# board.net
KiCad netlist of a schematic drawn in EAGLE
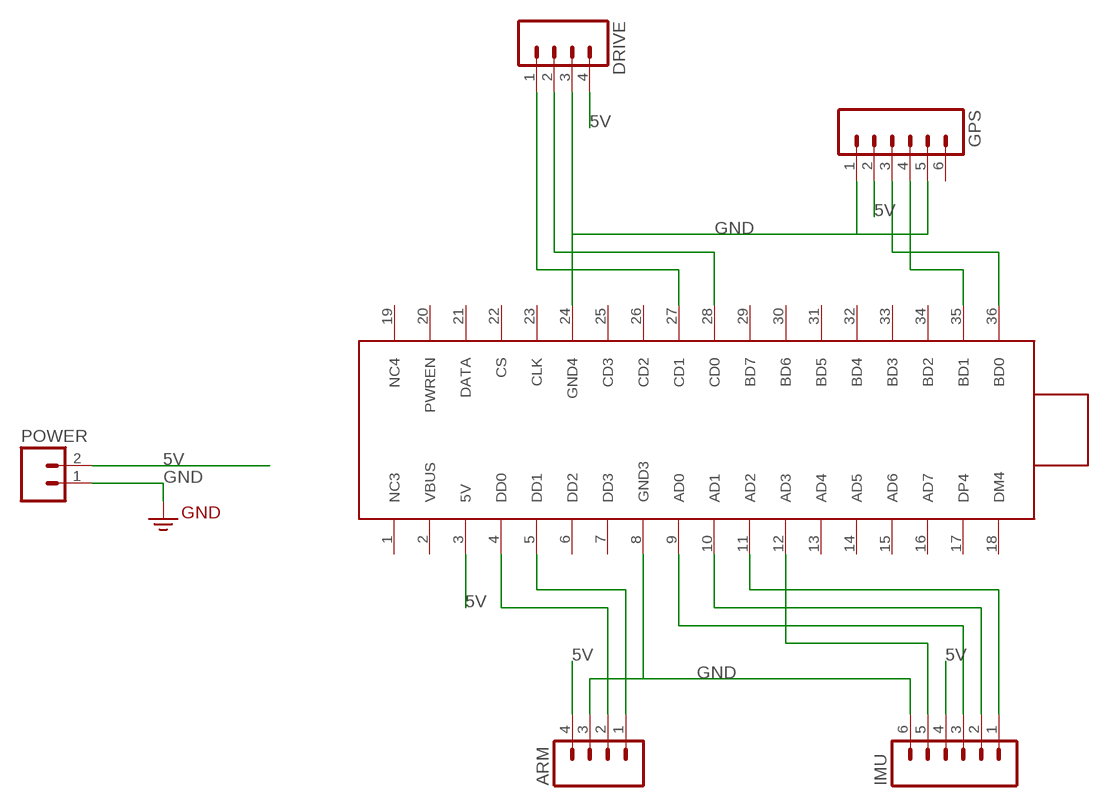
[diagram p0: schematic, sheet 1]

(export (version "E")
  (design (tool "Eeschema 10.0.6"))
  (components
    (comp (ref "ARM")
      (value "M04PTH")
      (footprint "eagle-import:1X04")
      (libsource (lib "eagle-import") (part "M04PTH"))
    )
    (comp (ref "DRIVE")
      (value "M04PTH")
      (footprint "eagle-import:1X04")
      (libsource (lib "eagle-import") (part "M04PTH"))
    )
    (comp (ref "GPS")
      (value "M06SILK_FEMALE_PTH")
      (footprint "eagle-import:1X06")
      (libsource (lib "eagle-import") (part "M06SILK_FEMALE_PTH"))
    )
    (comp (ref "IMU")
      (value "M06SILK_FEMALE_PTH")
      (footprint "eagle-import:1X06")
      (libsource (lib "eagle-import") (part "M06SILK_FEMALE_PTH"))
    )
    (comp (ref "POWER")
      (value "M02PTH")
      (footprint "eagle-import:1X02")
      (libsource (lib "eagle-import") (part "M02PTH"))
    )
    (comp (ref "U$1")
      (value "HUB")
      (footprint "eagle-import:HUB")
      (libsource (lib "eagle-import") (part "HUB"))
    )
  )
  (nets
    (net (code "1") (name "/5V") (class "Default")
      (node (ref "ARM") (pin "4") (pinfunction "4_4") (pintype "passive"))
      (node (ref "DRIVE") (pin "4") (pinfunction "4_4") (pintype "passive"))
      (node (ref "GPS") (pin "2") (pinfunction "2_2") (pintype "passive"))
      (node (ref "IMU") (pin "4") (pinfunction "4_4") (pintype "passive"))
      (node (ref "POWER") (pin "2") (pinfunction "2_2") (pintype "passive"))
      (node (ref "U$1") (pin "3") (pinfunction "5V_3") (pintype "bidirectional"))
    )
    (net (code "2") (name "GND2") (class "Default")
      (node (ref "ARM") (pin "3") (pinfunction "3_3") (pintype "passive"))
      (node (ref "DRIVE") (pin "3") (pinfunction "3_3") (pintype "passive"))
      (node (ref "GPS") (pin "1") (pinfunction "1_1") (pintype "passive"))
      (node (ref "GPS") (pin "5") (pinfunction "5_5") (pintype "passive"))
      (node (ref "IMU") (pin "6") (pinfunction "6_6") (pintype "passive"))
      (node (ref "POWER") (pin "1") (pinfunction "1_1") (pintype "passive"))
      (node (ref "U$1") (pin "24") (pinfunction "GND4_24") (pintype "bidirectional"))
      (node (ref "U$1") (pin "8") (pinfunction "GND3_8") (pintype "bidirectional"))
    )
    (net (code "3") (name "Net-(U$1-AD0)") (class "Default")
      (node (ref "IMU") (pin "3") (pinfunction "3_3") (pintype "passive"))
      (node (ref "U$1") (pin "9") (pinfunction "AD0_9") (pintype "bidirectional"))
    )
    (net (code "4") (name "Net-(U$1-AD1)") (class "Default")
      (node (ref "IMU") (pin "2") (pinfunction "2_2") (pintype "passive"))
      (node (ref "U$1") (pin "10") (pinfunction "AD1_10") (pintype "bidirectional"))
    )
    (net (code "5") (name "Net-(U$1-AD2)") (class "Default")
      (node (ref "IMU") (pin "1") (pinfunction "1_1") (pintype "passive"))
      (node (ref "U$1") (pin "11") (pinfunction "AD2_11") (pintype "bidirectional"))
    )
    (net (code "6") (name "Net-(U$1-AD3)") (class "Default")
      (node (ref "IMU") (pin "5") (pinfunction "5_5") (pintype "passive"))
      (node (ref "U$1") (pin "12") (pinfunction "AD3_12") (pintype "bidirectional"))
    )
    (net (code "7") (name "Net-(U$1-BD0)") (class "Default")
      (node (ref "GPS") (pin "3") (pinfunction "3_3") (pintype "passive"))
      (node (ref "U$1") (pin "36") (pinfunction "BD0_36") (pintype "bidirectional"))
    )
    (net (code "8") (name "Net-(U$1-BD1)") (class "Default")
      (node (ref "GPS") (pin "4") (pinfunction "4_4") (pintype "passive"))
      (node (ref "U$1") (pin "35") (pinfunction "BD1_35") (pintype "bidirectional"))
    )
    (net (code "9") (name "Net-(U$1-CD0)") (class "Default")
      (node (ref "DRIVE") (pin "2") (pinfunction "2_2") (pintype "passive"))
      (node (ref "U$1") (pin "28") (pinfunction "CD0_28") (pintype "bidirectional"))
    )
    (net (code "10") (name "Net-(U$1-CD1)") (class "Default")
      (node (ref "DRIVE") (pin "1") (pinfunction "1_1") (pintype "passive"))
      (node (ref "U$1") (pin "27") (pinfunction "CD1_27") (pintype "bidirectional"))
    )
    (net (code "11") (name "Net-(U$1-DD0)") (class "Default")
      (node (ref "ARM") (pin "2") (pinfunction "2_2") (pintype "passive"))
      (node (ref "U$1") (pin "4") (pinfunction "DD0_4") (pintype "bidirectional"))
    )
    (net (code "12") (name "Net-(U$1-DD1)") (class "Default")
      (node (ref "ARM") (pin "1") (pinfunction "1_1") (pintype "passive"))
      (node (ref "U$1") (pin "5") (pinfunction "DD1_5") (pintype "bidirectional"))
    )
    (net (code "13") (name "unconnected-(GPS-Pad6)") (class "Default")
      (node (ref "GPS") (pin "6") (pinfunction "6_6") (pintype "passive"))
    )
    (net (code "14") (name "unconnected-(U$1-AD4-Pad13)") (class "Default")
      (node (ref "U$1") (pin "13") (pinfunction "AD4_13") (pintype "bidirectional"))
    )
    (net (code "15") (name "unconnected-(U$1-AD5-Pad14)") (class "Default")
      (node (ref "U$1") (pin "14") (pinfunction "AD5_14") (pintype "bidirectional"))
    )
    (net (code "16") (name "unconnected-(U$1-AD6-Pad15)") (class "Default")
      (node (ref "U$1") (pin "15") (pinfunction "AD6_15") (pintype "bidirectional"))
    )
    (net (code "17") (name "unconnected-(U$1-AD7-Pad16)") (class "Default")
      (node (ref "U$1") (pin "16") (pinfunction "AD7_16") (pintype "bidirectional"))
    )
    (net (code "18") (name "unconnected-(U$1-BD2-Pad34)") (class "Default")
      (node (ref "U$1") (pin "34") (pinfunction "BD2_34") (pintype "bidirectional"))
    )
    (net (code "19") (name "unconnected-(U$1-BD3-Pad33)") (class "Default")
      (node (ref "U$1") (pin "33") (pinfunction "BD3_33") (pintype "bidirectional"))
    )
    (net (code "20") (name "unconnected-(U$1-BD4-Pad32)") (class "Default")
      (node (ref "U$1") (pin "32") (pinfunction "BD4_32") (pintype "bidirectional"))
    )
    (net (code "21") (name "unconnected-(U$1-BD5-Pad31)") (class "Default")
      (node (ref "U$1") (pin "31") (pinfunction "BD5_31") (pintype "bidirectional"))
    )
    (net (code "22") (name "unconnected-(U$1-BD6-Pad30)") (class "Default")
      (node (ref "U$1") (pin "30") (pinfunction "BD6_30") (pintype "bidirectional"))
    )
    (net (code "23") (name "unconnected-(U$1-BD7-Pad29)") (class "Default")
      (node (ref "U$1") (pin "29") (pinfunction "BD7_29") (pintype "bidirectional"))
    )
    (net (code "24") (name "unconnected-(U$1-CD2-Pad26)") (class "Default")
      (node (ref "U$1") (pin "26") (pinfunction "CD2_26") (pintype "bidirectional"))
    )
    (net (code "25") (name "unconnected-(U$1-CD3-Pad25)") (class "Default")
      (node (ref "U$1") (pin "25") (pinfunction "CD3_25") (pintype "bidirectional"))
    )
    (net (code "26") (name "unconnected-(U$1-CLK-Pad23)") (class "Default")
      (node (ref "U$1") (pin "23") (pinfunction "CLK_23") (pintype "bidirectional"))
    )
    (net (code "27") (name "unconnected-(U$1-CS-Pad22)") (class "Default")
      (node (ref "U$1") (pin "22") (pinfunction "CS_22") (pintype "bidirectional"))
    )
    (net (code "28") (name "unconnected-(U$1-DATA-Pad21)") (class "Default")
      (node (ref "U$1") (pin "21") (pinfunction "DATA_21") (pintype "bidirectional"))
    )
    (net (code "29") (name "unconnected-(U$1-DD2-Pad6)") (class "Default")
      (node (ref "U$1") (pin "6") (pinfunction "DD2_6") (pintype "bidirectional"))
    )
    (net (code "30") (name "unconnected-(U$1-DD3-Pad7)") (class "Default")
      (node (ref "U$1") (pin "7") (pinfunction "DD3_7") (pintype "bidirectional"))
    )
    (net (code "31") (name "unconnected-(U$1-DM4-Pad18)") (class "Default")
      (node (ref "U$1") (pin "18") (pinfunction "DM4_18") (pintype "bidirectional"))
    )
    (net (code "32") (name "unconnected-(U$1-DP4-Pad17)") (class "Default")
      (node (ref "U$1") (pin "17") (pinfunction "DP4_17") (pintype "bidirectional"))
    )
    (net (code "33") (name "unconnected-(U$1-NC3-Pad1)") (class "Default")
      (node (ref "U$1") (pin "1") (pinfunction "NC3_1") (pintype "bidirectional"))
    )
    (net (code "34") (name "unconnected-(U$1-NC4-Pad19)") (class "Default")
      (node (ref "U$1") (pin "19") (pinfunction "NC4_19") (pintype "bidirectional"))
    )
    (net (code "35") (name "unconnected-(U$1-PWREN-Pad20)") (class "Default")
      (node (ref "U$1") (pin "20") (pinfunction "PWREN_20") (pintype "bidirectional"))
    )
    (net (code "36") (name "unconnected-(U$1-VBUS-Pad2)") (class "Default")
      (node (ref "U$1") (pin "2") (pinfunction "VBUS_2") (pintype "bidirectional"))
    )
  )
)
